# JS7628_base_PWM_LED_IR_KEY_v1_0.net
KiCad netlist of a schematic drawn in Altium Designer
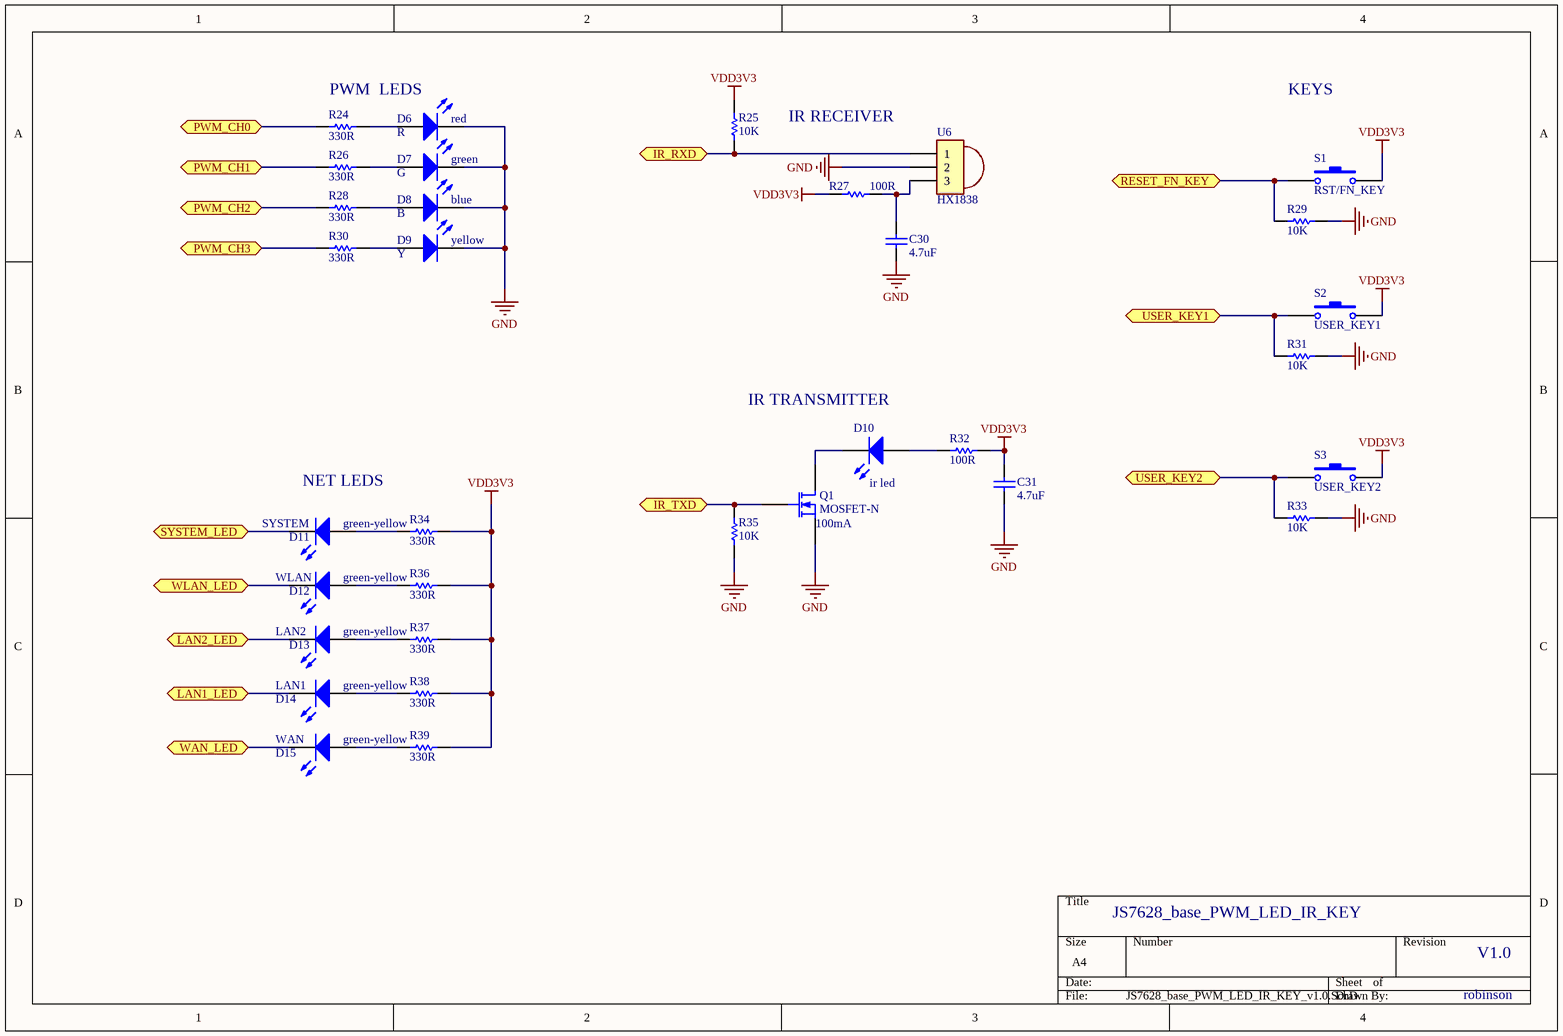
[diagram p0: JS7628_base_PWM_LED_IR_KEY_v1.0.SchDoc]

(export (version "E")
  (design (tool "Eeschema 10.0.6"))
  (components
    (comp (ref "C30")
      (value "4.7uF")
      (footprint "0603")
      (fields (field (name "Comment") "CAP-SMT"))
      (libsource (lib "MyMiscellaneousDevice") (part "CAP-SMT"))
    )
    (comp (ref "C31")
      (value "4.7uF")
      (footprint "0603")
      (fields (field (name "Comment") "CAP-SMT"))
      (libsource (lib "MyMiscellaneousDevice") (part "CAP-SMT"))
    )
    (comp (ref "D6")
      (value "R")
      (footprint "0805-LED")
      (fields (field (name "ALTIUM_VALUE") "red"))
      (libsource (lib "MyMiscellaneousDevice") (part "LED"))
    )
    (comp (ref "D7")
      (value "G")
      (footprint "0805-LED")
      (fields (field (name "ALTIUM_VALUE") "green"))
      (libsource (lib "MyMiscellaneousDevice") (part "LED"))
    )
    (comp (ref "D8")
      (value "B")
      (footprint "0805-LED")
      (fields (field (name "ALTIUM_VALUE") "blue"))
      (libsource (lib "MyMiscellaneousDevice") (part "LED"))
    )
    (comp (ref "D9")
      (value "Y")
      (footprint "0805-LED")
      (fields (field (name "ALTIUM_VALUE") "yellow"))
      (libsource (lib "MyMiscellaneousDevice") (part "LED"))
    )
    (comp (ref "D10")
      (value "ir led")
      (footprint "LED-5mm-90d")
      (fields (field (name "Comment") "LED"))
      (libsource (lib "MyMiscellaneousDevice") (part "LED"))
    )
    (comp (ref "D11")
      (value "SYSTEM")
      (footprint "0805-LED")
      (fields (field (name "ALTIUM_VALUE") "green-yellow"))
      (libsource (lib "MyMiscellaneousDevice") (part "LED"))
    )
    (comp (ref "D12")
      (value "WLAN")
      (footprint "0805-LED")
      (fields (field (name "ALTIUM_VALUE") "green-yellow"))
      (libsource (lib "MyMiscellaneousDevice") (part "LED"))
    )
    (comp (ref "D13")
      (value "LAN2")
      (footprint "0805-LED")
      (fields (field (name "ALTIUM_VALUE") "green-yellow"))
      (libsource (lib "MyMiscellaneousDevice") (part "LED"))
    )
    (comp (ref "D14")
      (value "LAN1")
      (footprint "0805-LED")
      (fields (field (name "ALTIUM_VALUE") "green-yellow"))
      (libsource (lib "MyMiscellaneousDevice") (part "LED"))
    )
    (comp (ref "D15")
      (value "WAN")
      (footprint "0805-LED")
      (fields (field (name "ALTIUM_VALUE") "green-yellow"))
      (libsource (lib "MyMiscellaneousDevice") (part "LED"))
    )
    (comp (ref "Q1")
      (value "MOSFET-N")
      (footprint "MyMiscellaneousDevice:SOT23-3P")
      (description "N-Channel MOSFET")
      (fields
        (field (name "ALTIUM_VALUE") "100mA")
        (field (name "PART NUMBER") "AO3400")
        (field (name "PUBLISHER") "Altium Limited")
      )
      (libsource (lib "MyMiscellaneousDevice") (part "MOSFET-N"))
    )
    (comp (ref "R24")
      (value "330R")
      (footprint "0603")
      (fields (field (name "Comment") "RES-SMT"))
      (libsource (lib "MyMiscellaneousDevice") (part "RES-SMT"))
    )
    (comp (ref "R25")
      (value "10K")
      (footprint "0603")
      (fields (field (name "Comment") "RES-SMT"))
      (libsource (lib "MyMiscellaneousDevice") (part "RES-SMT"))
    )
    (comp (ref "R26")
      (value "330R")
      (footprint "0603")
      (fields (field (name "Comment") "RES-SMT"))
      (libsource (lib "MyMiscellaneousDevice") (part "RES-SMT"))
    )
    (comp (ref "R27")
      (value "100R")
      (footprint "0603")
      (fields (field (name "Comment") "RES-SMT"))
      (libsource (lib "MyMiscellaneousDevice") (part "RES-SMT"))
    )
    (comp (ref "R28")
      (value "330R")
      (footprint "0603")
      (fields (field (name "Comment") "RES-SMT"))
      (libsource (lib "MyMiscellaneousDevice") (part "RES-SMT"))
    )
    (comp (ref "R29")
      (value "10K")
      (footprint "0603")
      (fields (field (name "Comment") "RES-SMT"))
      (libsource (lib "MyMiscellaneousDevice") (part "RES-SMT"))
    )
    (comp (ref "R30")
      (value "330R")
      (footprint "0603")
      (fields (field (name "Comment") "RES-SMT"))
      (libsource (lib "MyMiscellaneousDevice") (part "RES-SMT"))
    )
    (comp (ref "R31")
      (value "10K")
      (footprint "0603")
      (fields (field (name "Comment") "RES-SMT"))
      (libsource (lib "MyMiscellaneousDevice") (part "RES-SMT"))
    )
    (comp (ref "R32")
      (value "100R")
      (footprint "0603")
      (fields (field (name "Comment") "RES-SMT"))
      (libsource (lib "MyMiscellaneousDevice") (part "RES-SMT"))
    )
    (comp (ref "R33")
      (value "10K")
      (footprint "0603")
      (fields (field (name "Comment") "RES-SMT"))
      (libsource (lib "MyMiscellaneousDevice") (part "RES-SMT"))
    )
    (comp (ref "R34")
      (value "330R")
      (footprint "0603")
      (fields (field (name "Comment") "RES-SMT"))
      (libsource (lib "MyMiscellaneousDevice") (part "RES-SMT"))
    )
    (comp (ref "R35")
      (value "10K")
      (footprint "0603")
      (fields (field (name "Comment") "RES-SMT"))
      (libsource (lib "MyMiscellaneousDevice") (part "RES-SMT"))
    )
    (comp (ref "R36")
      (value "330R")
      (footprint "0603")
      (fields (field (name "Comment") "RES-SMT"))
      (libsource (lib "MyMiscellaneousDevice") (part "RES-SMT"))
    )
    (comp (ref "R37")
      (value "330R")
      (footprint "0603")
      (fields (field (name "Comment") "RES-SMT"))
      (libsource (lib "MyMiscellaneousDevice") (part "RES-SMT"))
    )
    (comp (ref "R38")
      (value "330R")
      (footprint "0603")
      (fields (field (name "Comment") "RES-SMT"))
      (libsource (lib "MyMiscellaneousDevice") (part "RES-SMT"))
    )
    (comp (ref "R39")
      (value "330R")
      (footprint "0603")
      (fields (field (name "Comment") "RES-SMT"))
      (libsource (lib "MyMiscellaneousDevice") (part "RES-SMT"))
    )
    (comp (ref "S1")
      (value "RST/FN_KEY")
      (footprint "SW-2P")
      (libsource (lib "MyMiscellaneousConnector") (part "SW-2P"))
    )
    (comp (ref "S2")
      (value "USER_KEY1")
      (footprint "SW-2P")
      (libsource (lib "MyMiscellaneousConnector") (part "SW-2P"))
    )
    (comp (ref "S3")
      (value "USER_KEY2")
      (footprint "SW-2P")
      (libsource (lib "MyMiscellaneousConnector") (part "SW-2P"))
    )
    (comp (ref "U6")
      (value "HX1838")
      (footprint "HX1838")
      (libsource (lib "MyMiscellaneousDevice") (part "HX1838"))
    )
  )
  (nets
    (net (code "1") (name "/IR_RXD") (class "Default")
      (node (ref "R25") (pin "1") (pinfunction "1_1") (pintype "passive"))
      (node (ref "U6") (pin "1") (pinfunction "1_1") (pintype "passive"))
    )
    (net (code "2") (name "/IR_TXD") (class "Default")
      (node (ref "Q1") (pin "1") (pinfunction "G_1") (pintype "passive"))
      (node (ref "R35") (pin "2") (pinfunction "2_2") (pintype "passive"))
    )
    (net (code "3") (name "/LAN1_LED") (class "Default")
      (node (ref "D14") (pin "2") (pinfunction "K_2") (pintype "passive"))
    )
    (net (code "4") (name "/LAN2_LED") (class "Default")
      (node (ref "D13") (pin "2") (pinfunction "K_2") (pintype "passive"))
    )
    (net (code "5") (name "/PWM_CH0") (class "Default")
      (node (ref "R24") (pin "1") (pinfunction "1_1") (pintype "passive"))
    )
    (net (code "6") (name "/PWM_CH1") (class "Default")
      (node (ref "R26") (pin "1") (pinfunction "1_1") (pintype "passive"))
    )
    (net (code "7") (name "/PWM_CH2") (class "Default")
      (node (ref "R28") (pin "1") (pinfunction "1_1") (pintype "passive"))
    )
    (net (code "8") (name "/PWM_CH3") (class "Default")
      (node (ref "R30") (pin "1") (pinfunction "1_1") (pintype "passive"))
    )
    (net (code "9") (name "/RESET_FN_KEY") (class "Default")
      (node (ref "R29") (pin "1") (pinfunction "1_1") (pintype "passive"))
      (node (ref "S1") (pin "1") (pinfunction "1_1") (pintype "passive"))
    )
    (net (code "10") (name "/SYSTEM_LED") (class "Default")
      (node (ref "D11") (pin "2") (pinfunction "K_2") (pintype "passive"))
    )
    (net (code "11") (name "/USER_KEY1") (class "Default")
      (node (ref "R31") (pin "1") (pinfunction "1_1") (pintype "passive"))
      (node (ref "S2") (pin "1") (pinfunction "1_1") (pintype "passive"))
    )
    (net (code "12") (name "/USER_KEY2") (class "Default")
      (node (ref "R33") (pin "1") (pinfunction "1_1") (pintype "passive"))
      (node (ref "S3") (pin "1") (pinfunction "1_1") (pintype "passive"))
    )
    (net (code "13") (name "/WAN_LED") (class "Default")
      (node (ref "D15") (pin "2") (pinfunction "K_2") (pintype "passive"))
    )
    (net (code "14") (name "/WLAN_LED") (class "Default")
      (node (ref "D12") (pin "2") (pinfunction "K_2") (pintype "passive"))
    )
    (net (code "15") (name "GND") (class "Default")
      (node (ref "C30") (pin "1") (pinfunction "1_1") (pintype "passive"))
      (node (ref "C31") (pin "1") (pinfunction "1_1") (pintype "passive"))
      (node (ref "D6") (pin "2") (pinfunction "K_2") (pintype "passive"))
      (node (ref "D7") (pin "2") (pinfunction "K_2") (pintype "passive"))
      (node (ref "D8") (pin "2") (pinfunction "K_2") (pintype "passive"))
      (node (ref "D9") (pin "2") (pinfunction "K_2") (pintype "passive"))
      (node (ref "Q1") (pin "2") (pinfunction "S_2") (pintype "passive"))
      (node (ref "R29") (pin "2") (pinfunction "2_2") (pintype "passive"))
      (node (ref "R31") (pin "2") (pinfunction "2_2") (pintype "passive"))
      (node (ref "R33") (pin "2") (pinfunction "2_2") (pintype "passive"))
      (node (ref "R35") (pin "1") (pinfunction "1_1") (pintype "passive"))
      (node (ref "U6") (pin "2") (pinfunction "2_2") (pintype "passive"))
    )
    (net (code "16") (name "Net-(C30-Pad2)") (class "Default")
      (node (ref "C30") (pin "2") (pinfunction "2_2") (pintype "passive"))
      (node (ref "R27") (pin "2") (pinfunction "2_2") (pintype "passive"))
      (node (ref "U6") (pin "3") (pinfunction "3_3") (pintype "passive"))
    )
    (net (code "17") (name "Net-(D6-A)") (class "Default")
      (node (ref "D6") (pin "1") (pinfunction "A_1") (pintype "passive"))
      (node (ref "R24") (pin "2") (pinfunction "2_2") (pintype "passive"))
    )
    (net (code "18") (name "Net-(D7-A)") (class "Default")
      (node (ref "D7") (pin "1") (pinfunction "A_1") (pintype "passive"))
      (node (ref "R26") (pin "2") (pinfunction "2_2") (pintype "passive"))
    )
    (net (code "19") (name "Net-(D8-A)") (class "Default")
      (node (ref "D8") (pin "1") (pinfunction "A_1") (pintype "passive"))
      (node (ref "R28") (pin "2") (pinfunction "2_2") (pintype "passive"))
    )
    (net (code "20") (name "Net-(D9-A)") (class "Default")
      (node (ref "D9") (pin "1") (pinfunction "A_1") (pintype "passive"))
      (node (ref "R30") (pin "2") (pinfunction "2_2") (pintype "passive"))
    )
    (net (code "21") (name "Net-(D10-A)") (class "Default")
      (node (ref "D10") (pin "1") (pinfunction "A_1") (pintype "passive"))
      (node (ref "R32") (pin "2") (pinfunction "2_2") (pintype "passive"))
    )
    (net (code "22") (name "Net-(D10-K)") (class "Default")
      (node (ref "D10") (pin "2") (pinfunction "K_2") (pintype "passive"))
      (node (ref "Q1") (pin "3") (pinfunction "D_3") (pintype "passive"))
    )
    (net (code "23") (name "Net-(D11-A)") (class "Default")
      (node (ref "D11") (pin "1") (pinfunction "A_1") (pintype "passive"))
      (node (ref "R34") (pin "1") (pinfunction "1_1") (pintype "passive"))
    )
    (net (code "24") (name "Net-(D12-A)") (class "Default")
      (node (ref "D12") (pin "1") (pinfunction "A_1") (pintype "passive"))
      (node (ref "R36") (pin "1") (pinfunction "1_1") (pintype "passive"))
    )
    (net (code "25") (name "Net-(D13-A)") (class "Default")
      (node (ref "D13") (pin "1") (pinfunction "A_1") (pintype "passive"))
      (node (ref "R37") (pin "1") (pinfunction "1_1") (pintype "passive"))
    )
    (net (code "26") (name "Net-(D14-A)") (class "Default")
      (node (ref "D14") (pin "1") (pinfunction "A_1") (pintype "passive"))
      (node (ref "R38") (pin "1") (pinfunction "1_1") (pintype "passive"))
    )
    (net (code "27") (name "Net-(D15-A)") (class "Default")
      (node (ref "D15") (pin "1") (pinfunction "A_1") (pintype "passive"))
      (node (ref "R39") (pin "1") (pinfunction "1_1") (pintype "passive"))
    )
    (net (code "28") (name "VDD3V3") (class "Default")
      (node (ref "C31") (pin "2") (pinfunction "2_2") (pintype "passive"))
      (node (ref "R25") (pin "2") (pinfunction "2_2") (pintype "passive"))
      (node (ref "R27") (pin "1") (pinfunction "1_1") (pintype "passive"))
      (node (ref "R32") (pin "1") (pinfunction "1_1") (pintype "passive"))
      (node (ref "R34") (pin "2") (pinfunction "2_2") (pintype "passive"))
      (node (ref "R36") (pin "2") (pinfunction "2_2") (pintype "passive"))
      (node (ref "R37") (pin "2") (pinfunction "2_2") (pintype "passive"))
      (node (ref "R38") (pin "2") (pinfunction "2_2") (pintype "passive"))
      (node (ref "R39") (pin "2") (pinfunction "2_2") (pintype "passive"))
      (node (ref "S1") (pin "2") (pinfunction "2_2") (pintype "passive"))
      (node (ref "S2") (pin "2") (pinfunction "2_2") (pintype "passive"))
      (node (ref "S3") (pin "2") (pinfunction "2_2") (pintype "passive"))
    )
  )
)
